# SCH_ZX_WiFi_2022-08-20.net
KiCad netlist of a schematic drawn in EasyEDA
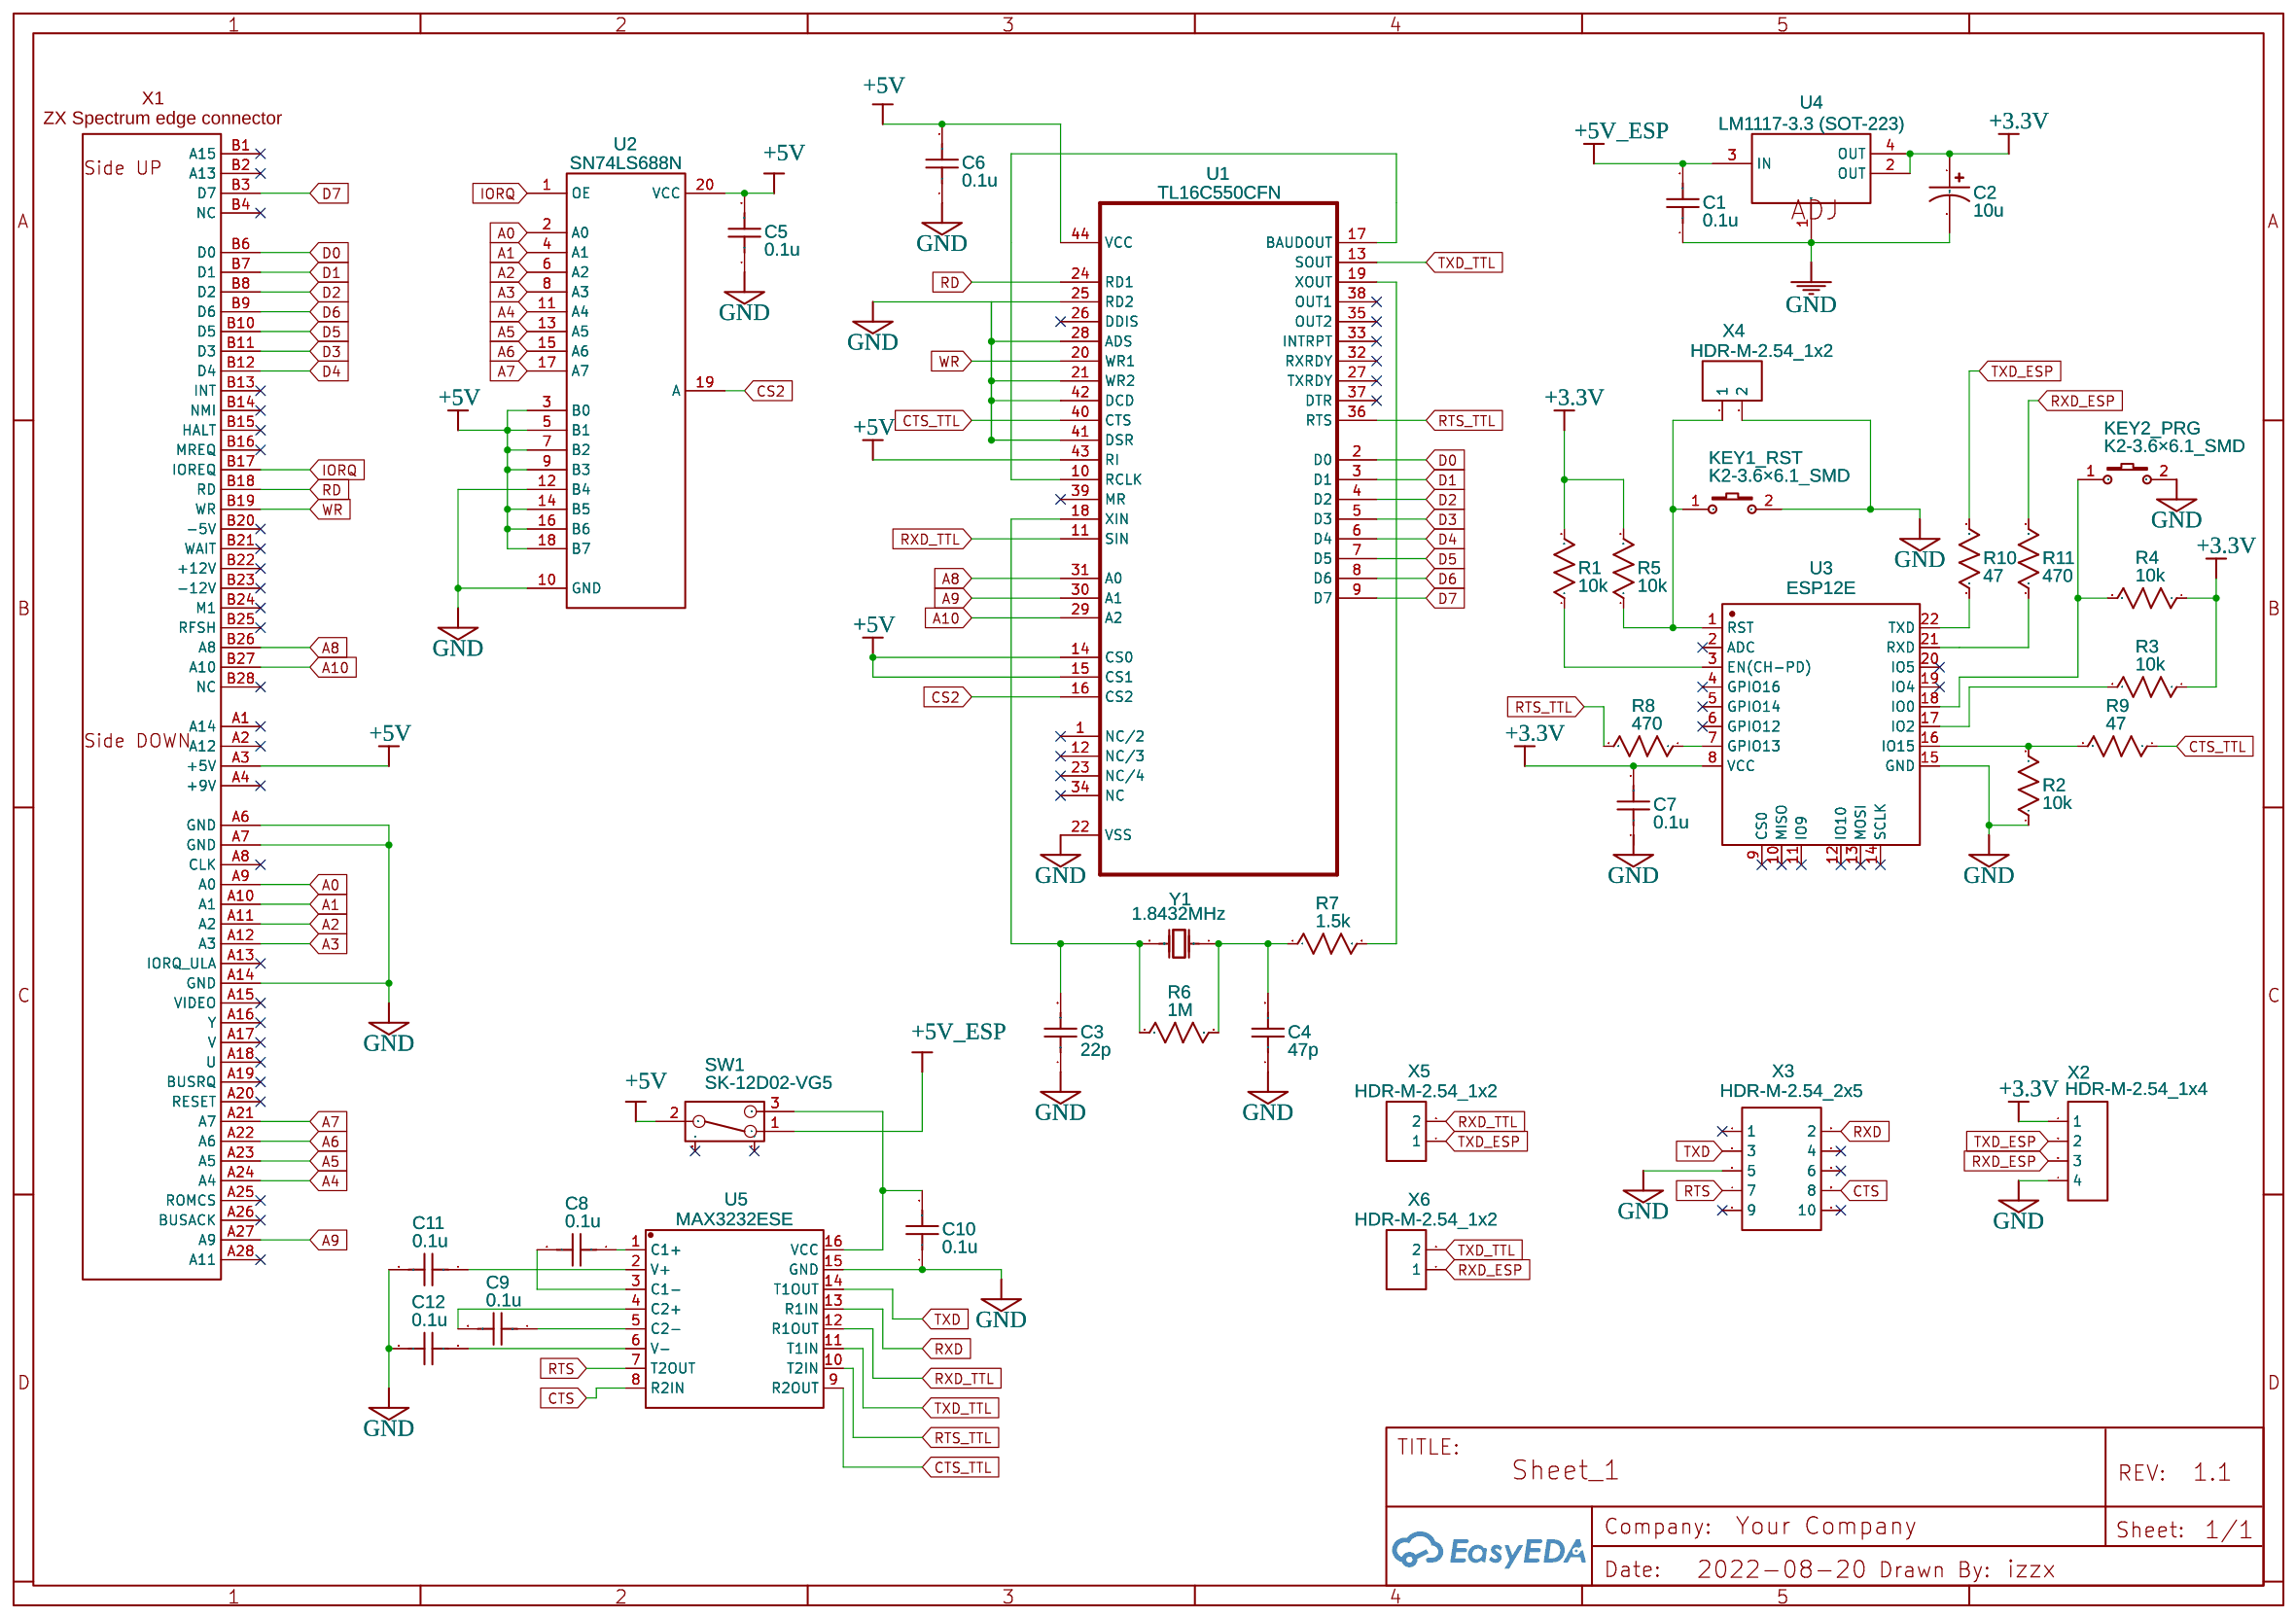
[diagram p0: schematic sheet]

(export (version "E")
  (design (tool "Eeschema 10.0.6"))
  (components
    (comp (ref "C1") (value "0.1u") (libsource (lib "") (part "C_0805_US_1")))
    (comp (ref "C2") (value "10u") (libsource (lib "") (part "C_Tan_SMD_A_US")))
    (comp (ref "C3") (value "22p") (libsource (lib "") (part "C_0805_US_1")))
    (comp (ref "C4") (value "47p") (libsource (lib "") (part "C_0805_US_1")))
    (comp (ref "C5") (value "0.1u") (libsource (lib "") (part "C_0805_US_1")))
    (comp (ref "C6") (value "0.1u") (libsource (lib "") (part "C_0805_US_1")))
    (comp (ref "C7") (value "0.1u") (libsource (lib "") (part "C_0805_US_1")))
    (comp (ref "C8") (value "0.1u") (libsource (lib "") (part "C_0805_US")))
    (comp (ref "C9") (value "0.1u") (libsource (lib "") (part "C_0805_US")))
    (comp (ref "C10") (value "0.1u") (libsource (lib "") (part "C_0805_US_1")))
    (comp (ref "C11") (value "0.1u") (libsource (lib "") (part "C_0805_US")))
    (comp (ref "C12") (value "0.1u") (libsource (lib "") (part "C_0805_US")))
    (comp (ref "KEY1_RST")
      (value "K2-3.6×6.1_SMD")
      (fields
        (field (name "BOM_Manufacturer Part") "K2-1107ST-A4SW-06")
        (field (name "BOM_Supplier Part") "C118141")
      )
      (libsource (lib "") (part "K2-3.6×6.1_SMD_1"))
    )
    (comp (ref "KEY2_PRG")
      (value "K2-3.6×6.1_SMD")
      (fields
        (field (name "BOM_Manufacturer Part") "K2-1107ST-A4SW-06")
        (field (name "BOM_Supplier Part") "C118141")
      )
      (libsource (lib "") (part "K2-3.6×6.1_SMD"))
    )
    (comp (ref "R1") (value "10k") (libsource (lib "") (part "R_0805_US")))
    (comp (ref "R2") (value "10k") (libsource (lib "") (part "R_0805_US")))
    (comp (ref "R3") (value "10k") (libsource (lib "") (part "R_0805_US_1")))
    (comp (ref "R4") (value "10k") (libsource (lib "") (part "R_0805_US_1")))
    (comp (ref "R5") (value "10k") (libsource (lib "") (part "R_0805_US")))
    (comp (ref "R6") (value "1M") (libsource (lib "") (part "R_0805_US_2")))
    (comp (ref "R7") (value "1.5k") (libsource (lib "") (part "R_0805_US_2")))
    (comp (ref "R8") (value "470") (libsource (lib "") (part "R_0805_US_1")))
    (comp (ref "R9") (value "47") (libsource (lib "") (part "R_0805_US_1")))
    (comp (ref "R10") (value "47") (libsource (lib "") (part "R_0805_US")))
    (comp (ref "R11") (value "470") (libsource (lib "") (part "R_0805_US")))
    (comp (ref "SW1")
      (value "SK-12D02-VG5")
      (fields (field (name "BOM_Supplier Part") "C136722"))
      (libsource (lib "") (part "SK-12D02-VG5"))
    )
    (comp (ref "U1") (value "TL16C550CFN") (libsource (lib "") (part "TL16C550CFN")))
    (comp (ref "U2") (value "SN74LS688N") (libsource (lib "") (part "SN74LS688N")))
    (comp (ref "U3") (value "ESP12E") (libsource (lib "") (part "ESP12E/F")))
    (comp (ref "U4")
      (value "LM1117-3.3 (SOT-223)")
      (fields
        (field (name "BOM_Manufacturer Part") "LM317G-AA3-R")
        (field (name "BOM_Supplier Part") "C19651")
      )
      (libsource (lib "") (part "LM317(SOT-223)"))
    )
    (comp (ref "U5")
      (value "MAX3232ESE")
      (fields (field (name "BOM_Supplier Part") "C2904738"))
      (libsource (lib "") (part "MAX3232ESE"))
    )
    (comp (ref "X1") (value "ZX SPECTRUM CONNECTOR") (libsource (lib "") (part "ZX SPECTRUM CONNECTOR")))
    (comp (ref "X2")
      (value "HDR-M-2.54_1x4")
      (fields (field (name "BOM_Supplier Part") "C124378"))
      (libsource (lib "") (part "HDR-M-2.54_1x4"))
    )
    (comp (ref "X3")
      (value "HDR-M-2.54_2x5")
      (fields (field (name "BOM_Supplier Part") "C178292"))
      (libsource (lib "") (part "HDR-M-2.54_2x5"))
    )
    (comp (ref "X4")
      (value "HDR-M-2.54_1x2")
      (fields (field (name "BOM_Supplier Part") "C124375"))
      (libsource (lib "") (part "HDR-M-2.54_1x2"))
    )
    (comp (ref "X5")
      (value "HDR-M-2.54_1x2")
      (fields (field (name "BOM_Supplier Part") "C124375"))
      (libsource (lib "") (part "HDR-M-2.54_1x2_1"))
    )
    (comp (ref "X6")
      (value "HDR-M-2.54_1x2")
      (fields (field (name "BOM_Supplier Part") "C124375"))
      (libsource (lib "") (part "HDR-M-2.54_1x2_1"))
    )
    (comp (ref "Y1")
      (value "1.8432MHz")
      (fields
        (field (name "BOM_Manufacturer Part") "X49UD3579MSD2SC")
        (field (name "BOM_Supplier Part") "C36564")
      )
      (libsource (lib "") (part "X49UD3579MSD2SC"))
    )
  )
  (nets
    (net (code "1") (name "+3.3V") (class "Default")
      (node (ref "C2") (pin "1") (pinfunction "1_1") (pintype "unspecified"))
      (node (ref "C7") (pin "2") (pinfunction "2_2") (pintype "unspecified"))
      (node (ref "R1") (pin "2") (pinfunction "2_2") (pintype "unspecified"))
      (node (ref "R3") (pin "1") (pinfunction "1_1") (pintype "unspecified"))
      (node (ref "R4") (pin "1") (pinfunction "1_1") (pintype "unspecified"))
      (node (ref "R5") (pin "2") (pinfunction "2_2") (pintype "unspecified"))
      (node (ref "U3") (pin "8") (pinfunction "VCC_8") (pintype "unspecified"))
      (node (ref "U4") (pin "2") (pinfunction "OUT_2") (pintype "passive"))
      (node (ref "U4") (pin "4") (pinfunction "OUT_4") (pintype "passive"))
      (node (ref "X2") (pin "1") (pinfunction "1_1") (pintype "unspecified"))
    )
    (net (code "2") (name "+5V") (class "Default")
      (node (ref "C5") (pin "2") (pinfunction "2_2") (pintype "unspecified"))
      (node (ref "C6") (pin "2") (pinfunction "2_2") (pintype "unspecified"))
      (node (ref "SW1") (pin "2") (pinfunction "2_2") (pintype "unspecified"))
      (node (ref "U1") (pin "14") (pinfunction "CS0_14") (pintype "input"))
      (node (ref "U1") (pin "15") (pinfunction "CS1_15") (pintype "input"))
      (node (ref "U1") (pin "43") (pinfunction "RI_43") (pintype "input"))
      (node (ref "U1") (pin "44") (pinfunction "VCC_44") (pintype "passive"))
      (node (ref "U2") (pin "14") (pinfunction "B5_14") (pintype "unspecified"))
      (node (ref "U2") (pin "16") (pinfunction "B6_16") (pintype "unspecified"))
      (node (ref "U2") (pin "18") (pinfunction "B7_18") (pintype "unspecified"))
      (node (ref "U2") (pin "20") (pinfunction "VCC_20") (pintype "passive"))
      (node (ref "U2") (pin "3") (pinfunction "B0_3") (pintype "unspecified"))
      (node (ref "U2") (pin "5") (pinfunction "B1_5") (pintype "unspecified"))
      (node (ref "U2") (pin "7") (pinfunction "B2_7") (pintype "unspecified"))
      (node (ref "U2") (pin "9") (pinfunction "B3_9") (pintype "unspecified"))
      (node (ref "X1") (pin "A3") (pinfunction "+5V_A3") (pintype "unspecified"))
    )
    (net (code "3") (name "+5V_ESP") (class "Default")
      (node (ref "C1") (pin "2") (pinfunction "2_2") (pintype "unspecified"))
      (node (ref "SW1") (pin "1") (pinfunction "1_1") (pintype "unspecified"))
      (node (ref "U4") (pin "3") (pinfunction "IN_3") (pintype "passive"))
    )
    (net (code "4") (name "A0") (class "Default")
      (node (ref "U2") (pin "2") (pinfunction "A0_2") (pintype "unspecified"))
      (node (ref "X1") (pin "A9") (pinfunction "A0_A9") (pintype "unspecified"))
    )
    (net (code "5") (name "A1") (class "Default")
      (node (ref "U2") (pin "4") (pinfunction "A1_4") (pintype "unspecified"))
      (node (ref "X1") (pin "A10") (pinfunction "A1_A10") (pintype "unspecified"))
    )
    (net (code "6") (name "A2") (class "Default")
      (node (ref "U2") (pin "6") (pinfunction "A2_6") (pintype "unspecified"))
      (node (ref "X1") (pin "A11") (pinfunction "A2_A11") (pintype "unspecified"))
    )
    (net (code "7") (name "A3") (class "Default")
      (node (ref "U2") (pin "8") (pinfunction "A3_8") (pintype "unspecified"))
      (node (ref "X1") (pin "A12") (pinfunction "A3_A12") (pintype "unspecified"))
    )
    (net (code "8") (name "A4") (class "Default")
      (node (ref "U2") (pin "11") (pinfunction "A4_11") (pintype "unspecified"))
      (node (ref "X1") (pin "A24") (pinfunction "A4_A24") (pintype "unspecified"))
    )
    (net (code "9") (name "A5") (class "Default")
      (node (ref "U2") (pin "13") (pinfunction "A5_13") (pintype "unspecified"))
      (node (ref "X1") (pin "A23") (pinfunction "A5_A23") (pintype "unspecified"))
    )
    (net (code "10") (name "A6") (class "Default")
      (node (ref "U2") (pin "15") (pinfunction "A6_15") (pintype "unspecified"))
      (node (ref "X1") (pin "A22") (pinfunction "A6_A22") (pintype "unspecified"))
    )
    (net (code "11") (name "A7") (class "Default")
      (node (ref "U2") (pin "17") (pinfunction "A7_17") (pintype "unspecified"))
      (node (ref "X1") (pin "A21") (pinfunction "A7_A21") (pintype "unspecified"))
    )
    (net (code "12") (name "A8") (class "Default")
      (node (ref "U1") (pin "31") (pinfunction "A0_31") (pintype "input"))
      (node (ref "X1") (pin "B26") (pinfunction "A8_B26") (pintype "unspecified"))
    )
    (net (code "13") (name "A9") (class "Default")
      (node (ref "U1") (pin "30") (pinfunction "A1_30") (pintype "input"))
      (node (ref "X1") (pin "A27") (pinfunction "A9_A27") (pintype "unspecified"))
    )
    (net (code "14") (name "A10") (class "Default")
      (node (ref "U1") (pin "29") (pinfunction "A2_29") (pintype "input"))
      (node (ref "X1") (pin "B27") (pinfunction "A10_B27") (pintype "unspecified"))
    )
    (net (code "15") (name "CS2") (class "Default")
      (node (ref "U1") (pin "16") (pinfunction "CS2_16") (pintype "input"))
      (node (ref "U2") (pin "19") (pinfunction "A_19") (pintype "output"))
    )
    (net (code "16") (name "CTS") (class "Default")
      (node (ref "U5") (pin "8") (pinfunction "R2IN_8") (pintype "unspecified"))
      (node (ref "X3") (pin "8") (pinfunction "8_8") (pintype "unspecified"))
    )
    (net (code "17") (name "CTS_TTL") (class "Default")
      (node (ref "R9") (pin "1") (pinfunction "1_1") (pintype "unspecified"))
      (node (ref "U1") (pin "40") (pinfunction "CTS_40") (pintype "input"))
      (node (ref "U5") (pin "9") (pinfunction "R2OUT_9") (pintype "unspecified"))
    )
    (net (code "18") (name "D0") (class "Default")
      (node (ref "U1") (pin "2") (pinfunction "D0_2") (pintype "unspecified"))
      (node (ref "X1") (pin "B6") (pinfunction "D0_B6") (pintype "bidirectional"))
    )
    (net (code "19") (name "D1") (class "Default")
      (node (ref "U1") (pin "3") (pinfunction "D1_3") (pintype "unspecified"))
      (node (ref "X1") (pin "B7") (pinfunction "D1_B7") (pintype "bidirectional"))
    )
    (net (code "20") (name "D2") (class "Default")
      (node (ref "U1") (pin "4") (pinfunction "D2_4") (pintype "unspecified"))
      (node (ref "X1") (pin "B8") (pinfunction "D2_B8") (pintype "bidirectional"))
    )
    (net (code "21") (name "D3") (class "Default")
      (node (ref "U1") (pin "5") (pinfunction "D3_5") (pintype "unspecified"))
      (node (ref "X1") (pin "B11") (pinfunction "D3_B11") (pintype "unspecified"))
    )
    (net (code "22") (name "D4") (class "Default")
      (node (ref "U1") (pin "6") (pinfunction "D4_6") (pintype "unspecified"))
      (node (ref "X1") (pin "B12") (pinfunction "D4_B12") (pintype "unspecified"))
    )
    (net (code "23") (name "D5") (class "Default")
      (node (ref "U1") (pin "7") (pinfunction "D5_7") (pintype "unspecified"))
      (node (ref "X1") (pin "B10") (pinfunction "D5_B10") (pintype "bidirectional"))
    )
    (net (code "24") (name "D6") (class "Default")
      (node (ref "U1") (pin "8") (pinfunction "D6_8") (pintype "unspecified"))
      (node (ref "X1") (pin "B9") (pinfunction "D6_B9") (pintype "unspecified"))
    )
    (net (code "25") (name "D7") (class "Default")
      (node (ref "U1") (pin "9") (pinfunction "D7_9") (pintype "unspecified"))
      (node (ref "X1") (pin "B3") (pinfunction "D7_B3") (pintype "bidirectional"))
    )
    (net (code "26") (name "GND") (class "Default")
      (node (ref "C1") (pin "1") (pinfunction "1_1") (pintype "unspecified"))
      (node (ref "C10") (pin "1") (pinfunction "1_1") (pintype "unspecified"))
      (node (ref "C11") (pin "2") (pinfunction "2_2") (pintype "unspecified"))
      (node (ref "C12") (pin "2") (pinfunction "2_2") (pintype "unspecified"))
      (node (ref "C2") (pin "2") (pinfunction "2_2") (pintype "unspecified"))
      (node (ref "C3") (pin "1") (pinfunction "1_1") (pintype "unspecified"))
      (node (ref "C4") (pin "1") (pinfunction "1_1") (pintype "unspecified"))
      (node (ref "C5") (pin "1") (pinfunction "1_1") (pintype "unspecified"))
      (node (ref "C6") (pin "1") (pinfunction "1_1") (pintype "unspecified"))
      (node (ref "C7") (pin "1") (pinfunction "1_1") (pintype "unspecified"))
      (node (ref "KEY1_RST") (pin "2") (pinfunction "2_2") (pintype "unspecified"))
      (node (ref "KEY2_PRG") (pin "2") (pinfunction "2_2") (pintype "unspecified"))
      (node (ref "R2") (pin "1") (pinfunction "1_1") (pintype "unspecified"))
      (node (ref "U1") (pin "21") (pinfunction "WR2_21") (pintype "input"))
      (node (ref "U1") (pin "22") (pinfunction "VSS_22") (pintype "passive"))
      (node (ref "U1") (pin "25") (pinfunction "RD2_25") (pintype "input"))
      (node (ref "U1") (pin "28") (pinfunction "ADS_28") (pintype "input"))
      (node (ref "U1") (pin "41") (pinfunction "DSR_41") (pintype "input"))
      (node (ref "U1") (pin "42") (pinfunction "DCD_42") (pintype "input"))
      (node (ref "U2") (pin "10") (pinfunction "GND_10") (pintype "passive"))
      (node (ref "U2") (pin "12") (pinfunction "B4_12") (pintype "unspecified"))
      (node (ref "U3") (pin "15") (pinfunction "GND_15") (pintype "unspecified"))
      (node (ref "U4") (pin "1") (pinfunction "ADJ_1") (pintype "passive"))
      (node (ref "U5") (pin "15") (pinfunction "GND_15") (pintype "unspecified"))
      (node (ref "X1") (pin "A14") (pinfunction "GND_A14") (pintype "unspecified"))
      (node (ref "X1") (pin "A6") (pinfunction "GND_A6") (pintype "unspecified"))
      (node (ref "X1") (pin "A7") (pinfunction "GND_A7") (pintype "unspecified"))
      (node (ref "X2") (pin "4") (pinfunction "4_4") (pintype "unspecified"))
      (node (ref "X3") (pin "5") (pinfunction "5_5") (pintype "unspecified"))
      (node (ref "X4") (pin "2") (pinfunction "2_2") (pintype "unspecified"))
    )
    (net (code "27") (name "IORQ") (class "Default")
      (node (ref "U2") (pin "1") (pinfunction "OE_1") (pintype "unspecified"))
      (node (ref "X1") (pin "B17") (pinfunction "IOREQ_B17") (pintype "unspecified"))
    )
    (net (code "28") (name "Net-(U1-BAUDOUT)") (class "Default")
      (node (ref "U1") (pin "10") (pinfunction "RCLK_10") (pintype "input"))
      (node (ref "U1") (pin "17") (pinfunction "BAUDOUT_17") (pintype "output"))
    )
    (net (code "29") (name "Net-(U1-XIN)") (class "Default")
      (node (ref "C3") (pin "2") (pinfunction "2_2") (pintype "unspecified"))
      (node (ref "R6") (pin "1") (pinfunction "1_1") (pintype "unspecified"))
      (node (ref "U1") (pin "18") (pinfunction "XIN_18") (pintype "input"))
      (node (ref "Y1") (pin "2") (pinfunction "OSC2_2") (pintype "input"))
    )
    (net (code "30") (name "Net-(U1-XOUT)") (class "Default")
      (node (ref "R7") (pin "2") (pinfunction "2_2") (pintype "unspecified"))
      (node (ref "U1") (pin "19") (pinfunction "XOUT_19") (pintype "output"))
    )
    (net (code "31") (name "Net-(U3-EN(CH-PD))") (class "Default")
      (node (ref "R1") (pin "1") (pinfunction "1_1") (pintype "unspecified"))
      (node (ref "U3") (pin "3") (pinfunction "EN(CH-PD)_3") (pintype "unspecified"))
    )
    (net (code "32") (name "Net-(U3-GPIO13)") (class "Default")
      (node (ref "R8") (pin "1") (pinfunction "1_1") (pintype "unspecified"))
      (node (ref "U3") (pin "7") (pinfunction "GPIO13_7") (pintype "unspecified"))
    )
    (net (code "33") (name "Net-(U3-IO0)") (class "Default")
      (node (ref "KEY2_PRG") (pin "1") (pinfunction "1_1") (pintype "unspecified"))
      (node (ref "R4") (pin "2") (pinfunction "2_2") (pintype "unspecified"))
      (node (ref "U3") (pin "18") (pinfunction "IO0_18") (pintype "unspecified"))
    )
    (net (code "34") (name "Net-(U3-IO2)") (class "Default")
      (node (ref "R3") (pin "2") (pinfunction "2_2") (pintype "unspecified"))
      (node (ref "U3") (pin "17") (pinfunction "IO2_17") (pintype "unspecified"))
    )
    (net (code "35") (name "Net-(U3-IO15)") (class "Default")
      (node (ref "R2") (pin "2") (pinfunction "2_2") (pintype "unspecified"))
      (node (ref "R9") (pin "2") (pinfunction "2_2") (pintype "unspecified"))
      (node (ref "U3") (pin "16") (pinfunction "IO15_16") (pintype "unspecified"))
    )
    (net (code "36") (name "Net-(U3-RST)") (class "Default")
      (node (ref "KEY1_RST") (pin "1") (pinfunction "1_1") (pintype "unspecified"))
      (node (ref "R5") (pin "1") (pinfunction "1_1") (pintype "unspecified"))
      (node (ref "U3") (pin "1") (pinfunction "RST_1") (pintype "unspecified"))
      (node (ref "X4") (pin "1") (pinfunction "1_1") (pintype "unspecified"))
    )
    (net (code "37") (name "Net-(U3-RXD)") (class "Default")
      (node (ref "R11") (pin "1") (pinfunction "1_1") (pintype "unspecified"))
      (node (ref "U3") (pin "21") (pinfunction "RXD_21") (pintype "unspecified"))
    )
    (net (code "38") (name "Net-(U3-TXD)") (class "Default")
      (node (ref "R10") (pin "1") (pinfunction "1_1") (pintype "unspecified"))
      (node (ref "U3") (pin "22") (pinfunction "TXD_22") (pintype "unspecified"))
    )
    (net (code "39") (name "Net-(U5-C1+)") (class "Default")
      (node (ref "C8") (pin "1") (pinfunction "1_1") (pintype "unspecified"))
      (node (ref "U5") (pin "1") (pinfunction "C1+_1") (pintype "unspecified"))
    )
    (net (code "40") (name "Net-(U5-C1-)") (class "Default")
      (node (ref "C8") (pin "2") (pinfunction "2_2") (pintype "unspecified"))
      (node (ref "U5") (pin "3") (pinfunction "C1-_3") (pintype "unspecified"))
    )
    (net (code "41") (name "Net-(U5-C2+)") (class "Default")
      (node (ref "C9") (pin "2") (pinfunction "2_2") (pintype "unspecified"))
      (node (ref "U5") (pin "4") (pinfunction "C2+_4") (pintype "unspecified"))
    )
    (net (code "42") (name "Net-(U5-C2-)") (class "Default")
      (node (ref "C9") (pin "1") (pinfunction "1_1") (pintype "unspecified"))
      (node (ref "U5") (pin "5") (pinfunction "C2-_5") (pintype "unspecified"))
    )
    (net (code "43") (name "Net-(U5-V+)") (class "Default")
      (node (ref "C11") (pin "1") (pinfunction "1_1") (pintype "unspecified"))
      (node (ref "U5") (pin "2") (pinfunction "V+_2") (pintype "unspecified"))
    )
    (net (code "44") (name "Net-(U5-V-)") (class "Default")
      (node (ref "C12") (pin "1") (pinfunction "1_1") (pintype "unspecified"))
      (node (ref "U5") (pin "6") (pinfunction "V-_6") (pintype "unspecified"))
    )
    (net (code "45") (name "Net-(U5-VCC)") (class "Default")
      (node (ref "C10") (pin "2") (pinfunction "2_2") (pintype "unspecified"))
      (node (ref "SW1") (pin "3") (pinfunction "3_3") (pintype "unspecified"))
      (node (ref "U5") (pin "16") (pinfunction "VCC_16") (pintype "unspecified"))
    )
    (net (code "46") (name "Net-(Y1-OSC1)") (class "Default")
      (node (ref "C4") (pin "2") (pinfunction "2_2") (pintype "unspecified"))
      (node (ref "R6") (pin "2") (pinfunction "2_2") (pintype "unspecified"))
      (node (ref "R7") (pin "1") (pinfunction "1_1") (pintype "unspecified"))
      (node (ref "Y1") (pin "1") (pinfunction "OSC1_1") (pintype "input"))
    )
    (net (code "47") (name "RD") (class "Default")
      (node (ref "U1") (pin "24") (pinfunction "RD1_24") (pintype "input"))
      (node (ref "X1") (pin "B18") (pinfunction "RD_B18") (pintype "unspecified"))
    )
    (net (code "48") (name "RTS") (class "Default")
      (node (ref "U5") (pin "7") (pinfunction "T2OUT_7") (pintype "unspecified"))
      (node (ref "X3") (pin "7") (pinfunction "7_7") (pintype "unspecified"))
    )
    (net (code "49") (name "RTS_TTL") (class "Default")
      (node (ref "R8") (pin "2") (pinfunction "2_2") (pintype "unspecified"))
      (node (ref "U1") (pin "36") (pinfunction "RTS_36") (pintype "output"))
      (node (ref "U5") (pin "10") (pinfunction "T2IN_10") (pintype "unspecified"))
    )
    (net (code "50") (name "RXD") (class "Default")
      (node (ref "U5") (pin "13") (pinfunction "R1IN_13") (pintype "unspecified"))
      (node (ref "X3") (pin "2") (pinfunction "2_2") (pintype "unspecified"))
    )
    (net (code "51") (name "RXD_ESP") (class "Default")
      (node (ref "R11") (pin "2") (pinfunction "2_2") (pintype "unspecified"))
      (node (ref "X2") (pin "3") (pinfunction "3_3") (pintype "unspecified"))
      (node (ref "X6") (pin "1") (pinfunction "1_1") (pintype "unspecified"))
    )
    (net (code "52") (name "RXD_TTL") (class "Default")
      (node (ref "U1") (pin "11") (pinfunction "SIN_11") (pintype "input"))
      (node (ref "U5") (pin "12") (pinfunction "R1OUT_12") (pintype "unspecified"))
      (node (ref "X5") (pin "2") (pinfunction "2_2") (pintype "unspecified"))
    )
    (net (code "53") (name "TXD") (class "Default")
      (node (ref "U5") (pin "14") (pinfunction "T1OUT_14") (pintype "unspecified"))
      (node (ref "X3") (pin "3") (pinfunction "3_3") (pintype "unspecified"))
    )
    (net (code "54") (name "TXD_ESP") (class "Default")
      (node (ref "R10") (pin "2") (pinfunction "2_2") (pintype "unspecified"))
      (node (ref "X2") (pin "2") (pinfunction "2_2") (pintype "unspecified"))
      (node (ref "X5") (pin "1") (pinfunction "1_1") (pintype "unspecified"))
    )
    (net (code "55") (name "TXD_TTL") (class "Default")
      (node (ref "U1") (pin "13") (pinfunction "SOUT_13") (pintype "output"))
      (node (ref "U5") (pin "11") (pinfunction "T1IN_11") (pintype "unspecified"))
      (node (ref "X6") (pin "2") (pinfunction "2_2") (pintype "unspecified"))
    )
    (net (code "56") (name "WR") (class "Default")
      (node (ref "U1") (pin "20") (pinfunction "WR1_20") (pintype "input"))
      (node (ref "X1") (pin "B19") (pinfunction "WR_B19") (pintype "unspecified"))
    )
    (net (code "57") (name "unconnected-(SW1-Pad4)") (class "Default")
      (node (ref "SW1") (pin "4") (pinfunction "4_4") (pintype "unspecified+no_connect"))
    )
    (net (code "58") (name "unconnected-(SW1-Pad5)") (class "Default")
      (node (ref "SW1") (pin "5") (pinfunction "5_5") (pintype "unspecified+no_connect"))
    )
    (net (code "59") (name "unconnected-(U1-DDIS-Pad26)") (class "Default")
      (node (ref "U1") (pin "26") (pinfunction "DDIS_26") (pintype "input+no_connect"))
    )
    (net (code "60") (name "unconnected-(U1-DTR-Pad37)") (class "Default")
      (node (ref "U1") (pin "37") (pinfunction "DTR_37") (pintype "output+no_connect"))
    )
    (net (code "61") (name "unconnected-(U1-INTRPT-Pad33)") (class "Default")
      (node (ref "U1") (pin "33") (pinfunction "INTRPT_33") (pintype "output+no_connect"))
    )
    (net (code "62") (name "unconnected-(U1-MR-Pad39)") (class "Default")
      (node (ref "U1") (pin "39") (pinfunction "MR_39") (pintype "input+no_connect"))
    )
    (net (code "63") (name "unconnected-(U1-NC-Pad34)") (class "Default")
      (node (ref "U1") (pin "34") (pinfunction "NC_34") (pintype "unspecified+no_connect"))
    )
    (net (code "64") (name "unconnected-(U1-NC{slash}2-Pad1)") (class "Default")
      (node (ref "U1") (pin "1") (pinfunction "NC/2_1") (pintype "unspecified+no_connect"))
    )
    (net (code "65") (name "unconnected-(U1-NC{slash}3-Pad12)") (class "Default")
      (node (ref "U1") (pin "12") (pinfunction "NC/3_12") (pintype "unspecified+no_connect"))
    )
    (net (code "66") (name "unconnected-(U1-NC{slash}4-Pad23)") (class "Default")
      (node (ref "U1") (pin "23") (pinfunction "NC/4_23") (pintype "unspecified+no_connect"))
    )
    (net (code "67") (name "unconnected-(U1-OUT1-Pad38)") (class "Default")
      (node (ref "U1") (pin "38") (pinfunction "OUT1_38") (pintype "output+no_connect"))
    )
    (net (code "68") (name "unconnected-(U1-OUT2-Pad35)") (class "Default")
      (node (ref "U1") (pin "35") (pinfunction "OUT2_35") (pintype "output+no_connect"))
    )
    (net (code "69") (name "unconnected-(U1-RXRDY-Pad32)") (class "Default")
      (node (ref "U1") (pin "32") (pinfunction "RXRDY_32") (pintype "output+no_connect"))
    )
    (net (code "70") (name "unconnected-(U1-TXRDY-Pad27)") (class "Default")
      (node (ref "U1") (pin "27") (pinfunction "TXRDY_27") (pintype "output+no_connect"))
    )
    (net (code "71") (name "unconnected-(U3-ADC-Pad2)") (class "Default")
      (node (ref "U3") (pin "2") (pinfunction "ADC_2") (pintype "unspecified+no_connect"))
    )
    (net (code "72") (name "unconnected-(U3-CS0-Pad9)") (class "Default")
      (node (ref "U3") (pin "9") (pinfunction "CS0_9") (pintype "unspecified+no_connect"))
    )
    (net (code "73") (name "unconnected-(U3-GPIO12-Pad6)") (class "Default")
      (node (ref "U3") (pin "6") (pinfunction "GPIO12_6") (pintype "unspecified+no_connect"))
    )
    (net (code "74") (name "unconnected-(U3-GPIO14-Pad5)") (class "Default")
      (node (ref "U3") (pin "5") (pinfunction "GPIO14_5") (pintype "unspecified+no_connect"))
    )
    (net (code "75") (name "unconnected-(U3-GPIO16-Pad4)") (class "Default")
      (node (ref "U3") (pin "4") (pinfunction "GPIO16_4") (pintype "unspecified+no_connect"))
    )
    (net (code "76") (name "unconnected-(U3-IO4-Pad19)") (class "Default")
      (node (ref "U3") (pin "19") (pinfunction "IO4_19") (pintype "unspecified+no_connect"))
    )
    (net (code "77") (name "unconnected-(U3-IO5-Pad20)") (class "Default")
      (node (ref "U3") (pin "20") (pinfunction "IO5_20") (pintype "unspecified+no_connect"))
    )
    (net (code "78") (name "unconnected-(U3-IO9-Pad11)") (class "Default")
      (node (ref "U3") (pin "11") (pinfunction "IO9_11") (pintype "unspecified+no_connect"))
    )
    (net (code "79") (name "unconnected-(U3-IO10-Pad12)") (class "Default")
      (node (ref "U3") (pin "12") (pinfunction "IO10_12") (pintype "unspecified+no_connect"))
    )
    (net (code "80") (name "unconnected-(U3-MISO-Pad10)") (class "Default")
      (node (ref "U3") (pin "10") (pinfunction "MISO_10") (pintype "unspecified+no_connect"))
    )
    (net (code "81") (name "unconnected-(U3-MOSI-Pad13)") (class "Default")
      (node (ref "U3") (pin "13") (pinfunction "MOSI_13") (pintype "unspecified+no_connect"))
    )
    (net (code "82") (name "unconnected-(U3-SCLK-Pad14)") (class "Default")
      (node (ref "U3") (pin "14") (pinfunction "SCLK_14") (pintype "unspecified+no_connect"))
    )
    (net (code "83") (name "unconnected-(X1-+9V-PadA4)") (class "Default")
      (node (ref "X1") (pin "A4") (pinfunction "+9V_A4") (pintype "unspecified+no_connect"))
    )
    (net (code "84") (name "unconnected-(X1-+12V-PadB22)") (class "Default")
      (node (ref "X1") (pin "B22") (pinfunction "+12V_B22") (pintype "unspecified+no_connect"))
    )
    (net (code "85") (name "unconnected-(X1--5V-PadB20)") (class "Default")
      (node (ref "X1") (pin "B20") (pinfunction "-5V_B20") (pintype "unspecified+no_connect"))
    )
    (net (code "86") (name "unconnected-(X1--12V-PadB23)") (class "Default")
      (node (ref "X1") (pin "B23") (pinfunction "-12V_B23") (pintype "unspecified+no_connect"))
    )
    (net (code "87") (name "unconnected-(X1-A11-PadA28)") (class "Default")
      (node (ref "X1") (pin "A28") (pinfunction "A11_A28") (pintype "unspecified+no_connect"))
    )
    (net (code "88") (name "unconnected-(X1-A12-PadA2)") (class "Default")
      (node (ref "X1") (pin "A2") (pinfunction "A12_A2") (pintype "unspecified+no_connect"))
    )
    (net (code "89") (name "unconnected-(X1-A13-PadB2)") (class "Default")
      (node (ref "X1") (pin "B2") (pinfunction "A13_B2") (pintype "output+no_connect"))
    )
    (net (code "90") (name "unconnected-(X1-A14-PadA1)") (class "Default")
      (node (ref "X1") (pin "A1") (pinfunction "A14_A1") (pintype "unspecified+no_connect"))
    )
    (net (code "91") (name "unconnected-(X1-A15-PadB1)") (class "Default")
      (node (ref "X1") (pin "B1") (pinfunction "A15_B1") (pintype "output+no_connect"))
    )
    (net (code "92") (name "unconnected-(X1-BUSACK-PadA26)") (class "Default")
      (node (ref "X1") (pin "A26") (pinfunction "BUSACK_A26") (pintype "unspecified+no_connect"))
    )
    (net (code "93") (name "unconnected-(X1-BUSRQ-PadA19)") (class "Default")
      (node (ref "X1") (pin "A19") (pinfunction "BUSRQ_A19") (pintype "unspecified+no_connect"))
    )
    (net (code "94") (name "unconnected-(X1-CLK-PadA8)") (class "Default")
      (node (ref "X1") (pin "A8") (pinfunction "CLK_A8") (pintype "unspecified+no_connect"))
    )
    (net (code "95") (name "unconnected-(X1-HALT-PadB15)") (class "Default")
      (node (ref "X1") (pin "B15") (pinfunction "HALT_B15") (pintype "unspecified+no_connect"))
    )
    (net (code "96") (name "unconnected-(X1-INT-PadB13)") (class "Default")
      (node (ref "X1") (pin "B13") (pinfunction "INT_B13") (pintype "unspecified+no_connect"))
    )
    (net (code "97") (name "unconnected-(X1-IORQ_ULA-PadA13)") (class "Default")
      (node (ref "X1") (pin "A13") (pinfunction "IORQ_ULA_A13") (pintype "unspecified+no_connect"))
    )
    (net (code "98") (name "unconnected-(X1-M1-PadB24)") (class "Default")
      (node (ref "X1") (pin "B24") (pinfunction "M1_B24") (pintype "unspecified+no_connect"))
    )
    (net (code "99") (name "unconnected-(X1-MREQ-PadB16)") (class "Default")
      (node (ref "X1") (pin "B16") (pinfunction "MREQ_B16") (pintype "unspecified+no_connect"))
    )
    (net (code "100") (name "unconnected-(X1-NC-PadB4)") (class "Default")
      (node (ref "X1") (pin "B4") (pinfunction "NC_B4") (pintype "unspecified+no_connect"))
    )
    (net (code "101") (name "unconnected-(X1-NC-PadB28)") (class "Default")
      (node (ref "X1") (pin "B28") (pinfunction "NC_B28") (pintype "unspecified+no_connect"))
    )
    (net (code "102") (name "unconnected-(X1-NMI-PadB14)") (class "Default")
      (node (ref "X1") (pin "B14") (pinfunction "NMI_B14") (pintype "unspecified+no_connect"))
    )
    (net (code "103") (name "unconnected-(X1-RESET-PadA20)") (class "Default")
      (node (ref "X1") (pin "A20") (pinfunction "RESET_A20") (pintype "unspecified+no_connect"))
    )
    (net (code "104") (name "unconnected-(X1-RFSH-PadB25)") (class "Default")
      (node (ref "X1") (pin "B25") (pinfunction "RFSH_B25") (pintype "unspecified+no_connect"))
    )
    (net (code "105") (name "unconnected-(X1-ROMCS-PadA25)") (class "Default")
      (node (ref "X1") (pin "A25") (pinfunction "ROMCS_A25") (pintype "unspecified+no_connect"))
    )
    (net (code "106") (name "unconnected-(X1-U-PadA18)") (class "Default")
      (node (ref "X1") (pin "A18") (pinfunction "U_A18") (pintype "unspecified+no_connect"))
    )
    (net (code "107") (name "unconnected-(X1-V-PadA17)") (class "Default")
      (node (ref "X1") (pin "A17") (pinfunction "V_A17") (pintype "unspecified+no_connect"))
    )
    (net (code "108") (name "unconnected-(X1-VIDEO-PadA15)") (class "Default")
      (node (ref "X1") (pin "A15") (pinfunction "VIDEO_A15") (pintype "unspecified+no_connect"))
    )
    (net (code "109") (name "unconnected-(X1-WAIT-PadB21)") (class "Default")
      (node (ref "X1") (pin "B21") (pinfunction "WAIT_B21") (pintype "unspecified+no_connect"))
    )
    (net (code "110") (name "unconnected-(X1-Y-PadA16)") (class "Default")
      (node (ref "X1") (pin "A16") (pinfunction "Y_A16") (pintype "unspecified+no_connect"))
    )
    (net (code "111") (name "unconnected-(X3-Pad1)") (class "Default")
      (node (ref "X3") (pin "1") (pinfunction "1_1") (pintype "unspecified+no_connect"))
    )
    (net (code "112") (name "unconnected-(X3-Pad4)") (class "Default")
      (node (ref "X3") (pin "4") (pinfunction "4_4") (pintype "unspecified+no_connect"))
    )
    (net (code "113") (name "unconnected-(X3-Pad6)") (class "Default")
      (node (ref "X3") (pin "6") (pinfunction "6_6") (pintype "unspecified+no_connect"))
    )
    (net (code "114") (name "unconnected-(X3-Pad9)") (class "Default")
      (node (ref "X3") (pin "9") (pinfunction "9_9") (pintype "unspecified+no_connect"))
    )
    (net (code "115") (name "unconnected-(X3-Pad10)") (class "Default")
      (node (ref "X3") (pin "10") (pinfunction "10_10") (pintype "unspecified+no_connect"))
    )
  )
)
